# Audio.net
KiCad netlist of a schematic drawn in Altium Designer
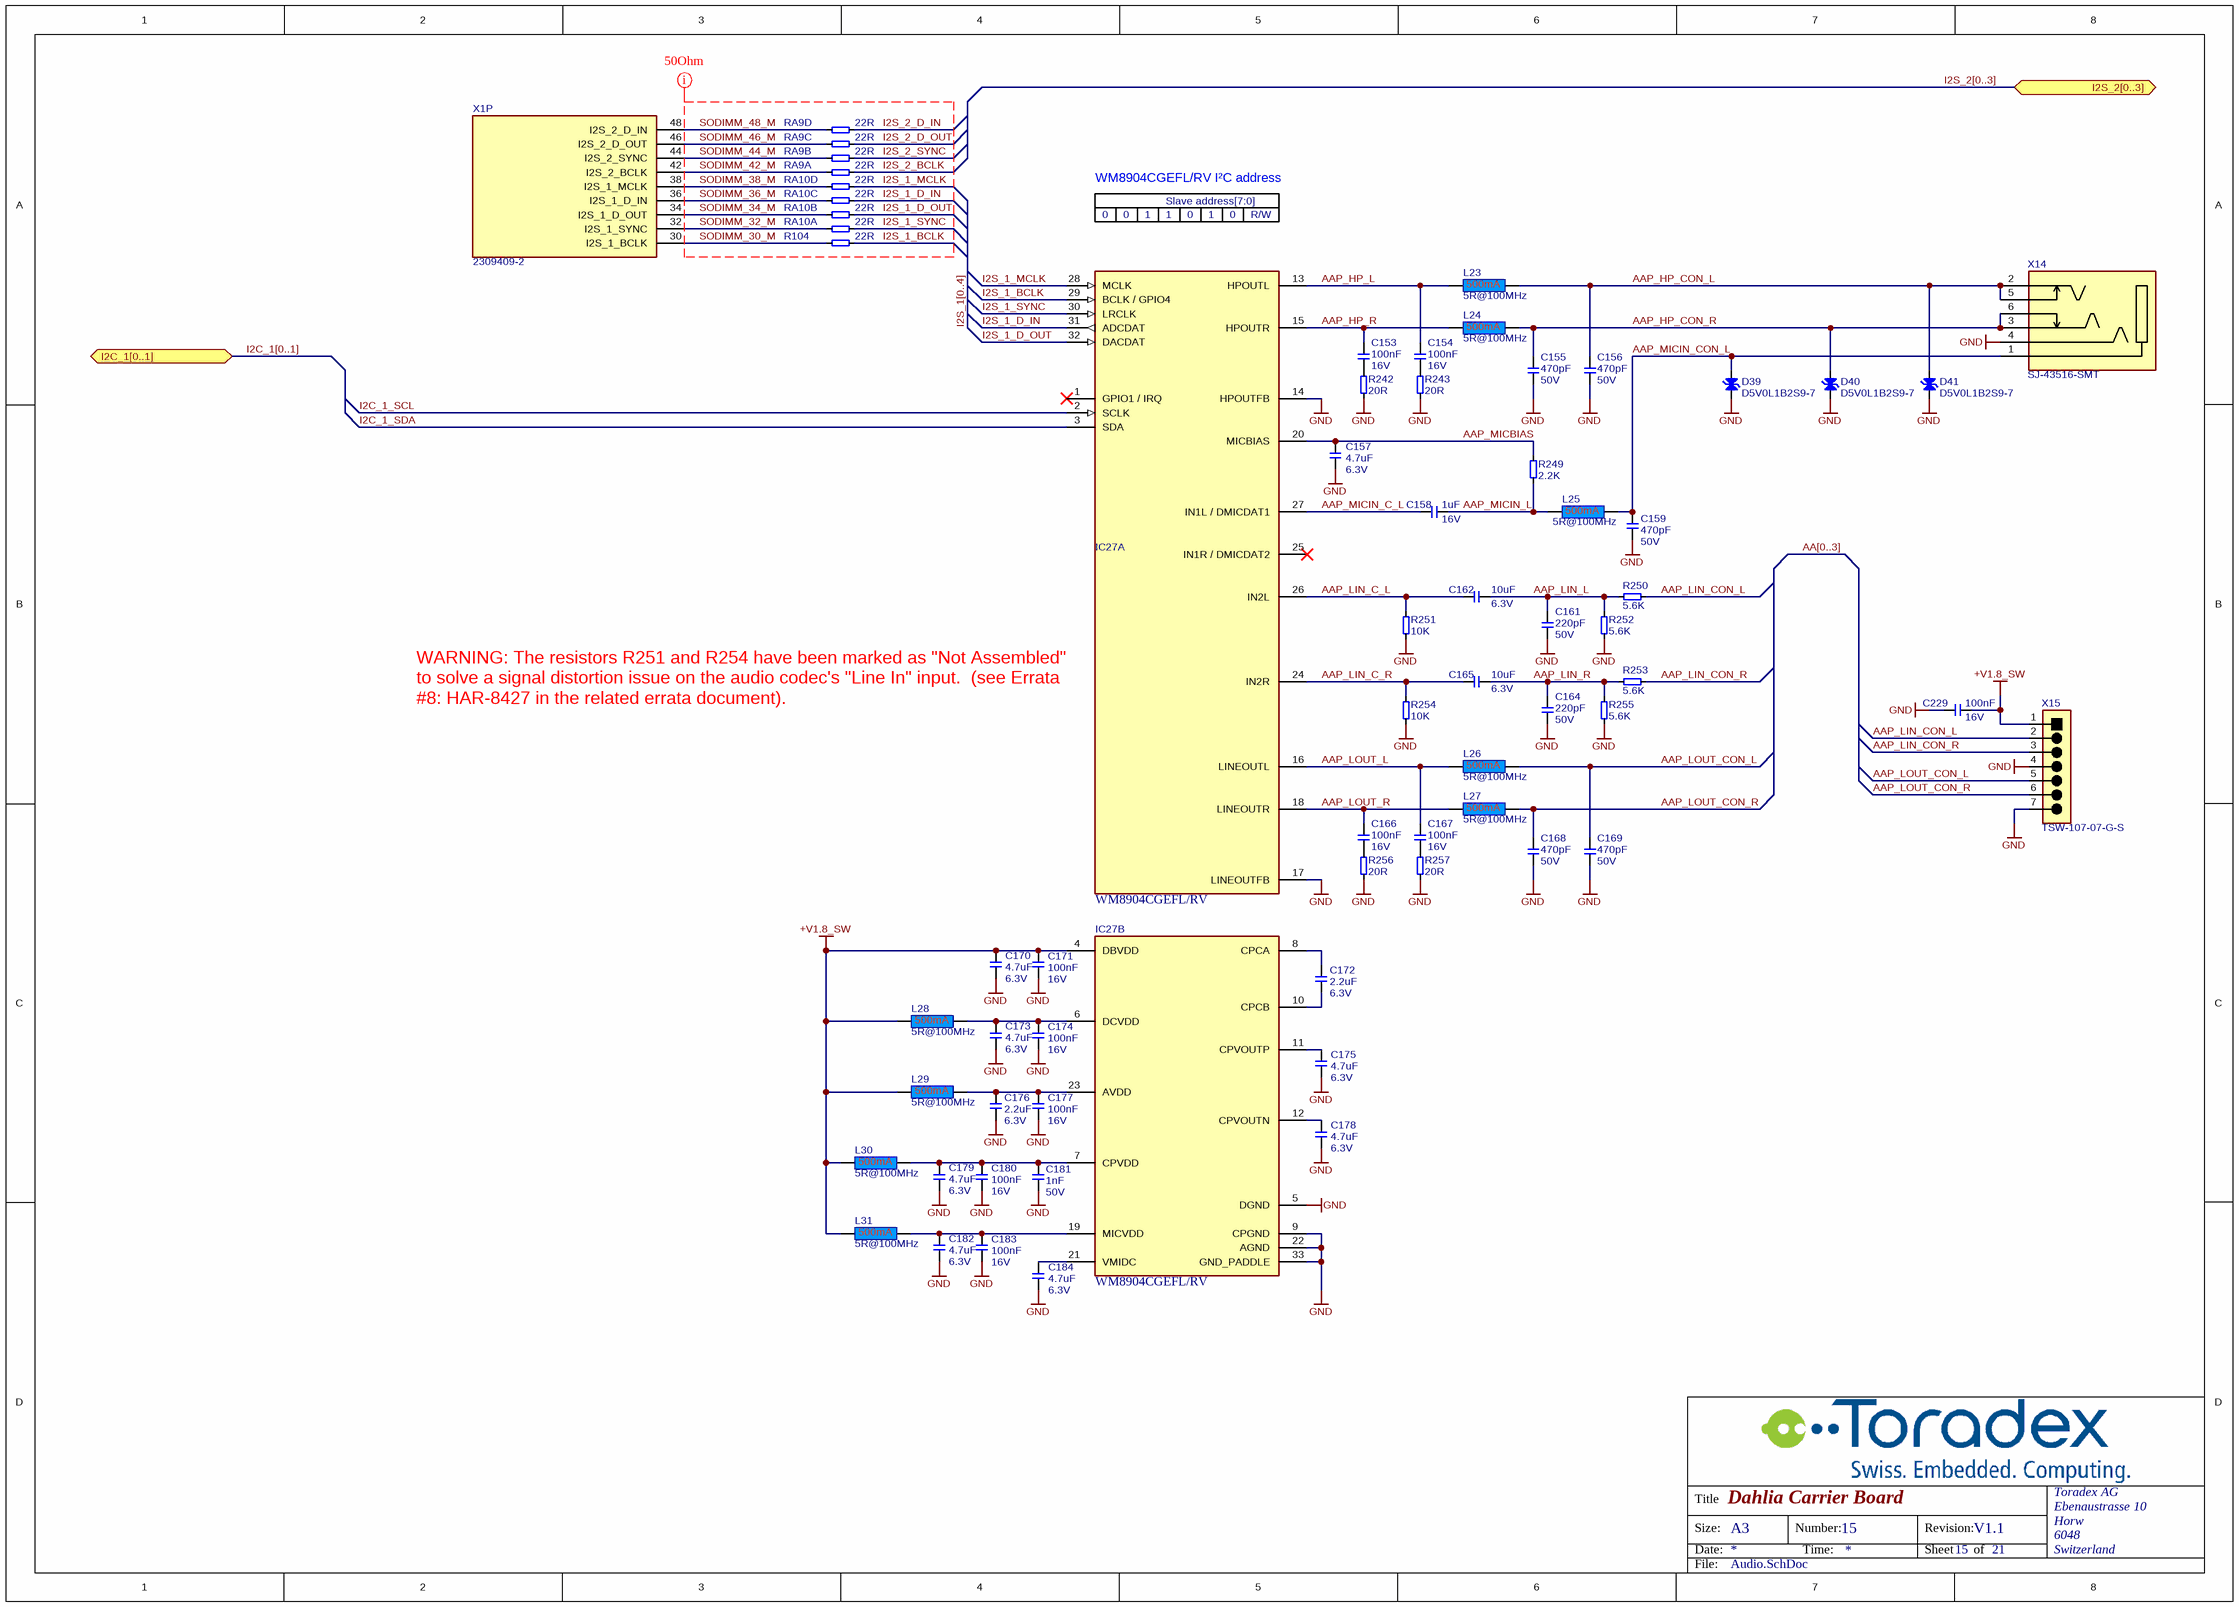
[diagram p0: Audio.SchDoc]

(export (version "E")
  (design (tool "Eeschema 10.0.6"))
  (components
    (comp (ref "C153")
      (value "100nF")
      (footprint "CAPC1005X60N")
      (description "Capacitor Ceramic X7R 100nF 16V 10% 0402")
      (fields (field (name "TOLERANCE") "10%") (field (name "RATING") "16V"))
      (libsource (lib "Dahlia Carrier Board") (part "C-X7R-100nF-16V-10%-0402"))
    )
    (comp (ref "C154")
      (value "100nF")
      (footprint "CAPC1005X60N")
      (description "Capacitor Ceramic X7R 100nF 16V 10% 0402")
      (fields (field (name "TOLERANCE") "10%") (field (name "RATING") "16V"))
      (libsource (lib "Dahlia Carrier Board") (part "C-X7R-100nF-16V-10%-0402"))
    )
    (comp (ref "C155")
      (value "470pF")
      (footprint "CAPC1005X60N")
      (description "Capacitor Ceramic X7R 470pF 50V 10% 0402")
      (fields (field (name "TOLERANCE") "10%") (field (name "RATING") "50V"))
      (libsource (lib "Dahlia Carrier Board") (part "C-X7R-470p-50V-10%-0402"))
    )
    (comp (ref "C156")
      (value "470pF")
      (footprint "CAPC1005X60N")
      (description "Capacitor Ceramic X7R 470pF 50V 10% 0402")
      (fields (field (name "TOLERANCE") "10%") (field (name "RATING") "50V"))
      (libsource (lib "Dahlia Carrier Board") (part "C-X7R-470p-50V-10%-0402"))
    )
    (comp (ref "C157")
      (value "4.7uF")
      (footprint "CAPC1005X60N")
      (description "Capacitor Ceramic X5R 4.7uF 6.3V 20% 0402")
      (fields (field (name "TOLERANCE") "20%") (field (name "RATING") "6.3V"))
      (libsource (lib "Dahlia Carrier Board") (part "C-X5R-4.7u-6.3V-20%-0402"))
    )
    (comp (ref "C158")
      (value "1uF")
      (footprint "CAPC1005X60N")
      (description "Capacitor Ceramic X5R 1uF 16V 20% 0402")
      (fields (field (name "TOLERANCE") "20%") (field (name "RATING") "16V"))
      (libsource (lib "Dahlia Carrier Board") (part "C-X5R-1uF-16V-20%-0402"))
    )
    (comp (ref "C159")
      (value "470pF")
      (footprint "CAPC1005X60N")
      (description "Capacitor Ceramic X7R 470pF 50V 10% 0402")
      (fields (field (name "TOLERANCE") "10%") (field (name "RATING") "50V"))
      (libsource (lib "Dahlia Carrier Board") (part "C-X7R-470p-50V-10%-0402"))
    )
    (comp (ref "C161")
      (value "220pF")
      (footprint "CAPC1005X60N")
      (description "Capacitor Ceramic X7R  220pF 50V 10% 0402")
      (fields (field (name "TOLERANCE") "10%") (field (name "RATING") "50V"))
      (libsource (lib "Dahlia Carrier Board") (part "C-X7R-220pF-50V-10%-0402"))
    )
    (comp (ref "C162")
      (value "10uF")
      (footprint "CAPC1005X60N")
      (description "Capacitor Ceramic X5R 10uF 6.3V 20% 0402")
      (fields (field (name "TOLERANCE") "20%") (field (name "RATING") "6.3V"))
      (libsource (lib "Dahlia Carrier Board") (part "C-X5R-10u-6.3V-20%-0402"))
    )
    (comp (ref "C164")
      (value "220pF")
      (footprint "CAPC1005X60N")
      (description "Capacitor Ceramic X7R  220pF 50V 10% 0402")
      (fields (field (name "TOLERANCE") "10%") (field (name "RATING") "50V"))
      (libsource (lib "Dahlia Carrier Board") (part "C-X7R-220pF-50V-10%-0402"))
    )
    (comp (ref "C165")
      (value "10uF")
      (footprint "CAPC1005X60N")
      (description "Capacitor Ceramic X5R 10uF 6.3V 20% 0402")
      (fields (field (name "TOLERANCE") "20%") (field (name "RATING") "6.3V"))
      (libsource (lib "Dahlia Carrier Board") (part "C-X5R-10u-6.3V-20%-0402"))
    )
    (comp (ref "C166")
      (value "100nF")
      (footprint "CAPC1005X60N")
      (description "Capacitor Ceramic X7R 100nF 16V 10% 0402")
      (fields (field (name "TOLERANCE") "10%") (field (name "RATING") "16V"))
      (libsource (lib "Dahlia Carrier Board") (part "C-X7R-100nF-16V-10%-0402"))
    )
    (comp (ref "C167")
      (value "100nF")
      (footprint "CAPC1005X60N")
      (description "Capacitor Ceramic X7R 100nF 16V 10% 0402")
      (fields (field (name "TOLERANCE") "10%") (field (name "RATING") "16V"))
      (libsource (lib "Dahlia Carrier Board") (part "C-X7R-100nF-16V-10%-0402"))
    )
    (comp (ref "C168")
      (value "470pF")
      (footprint "CAPC1005X60N")
      (description "Capacitor Ceramic X7R 470pF 50V 10% 0402")
      (fields (field (name "TOLERANCE") "10%") (field (name "RATING") "50V"))
      (libsource (lib "Dahlia Carrier Board") (part "C-X7R-470p-50V-10%-0402"))
    )
    (comp (ref "C169")
      (value "470pF")
      (footprint "CAPC1005X60N")
      (description "Capacitor Ceramic X7R 470pF 50V 10% 0402")
      (fields (field (name "TOLERANCE") "10%") (field (name "RATING") "50V"))
      (libsource (lib "Dahlia Carrier Board") (part "C-X7R-470p-50V-10%-0402"))
    )
    (comp (ref "C170")
      (value "4.7uF")
      (footprint "CAPC1005X60N")
      (description "Capacitor Ceramic X5R 4.7uF 6.3V 20% 0402")
      (fields (field (name "TOLERANCE") "20%") (field (name "RATING") "6.3V"))
      (libsource (lib "Dahlia Carrier Board") (part "C-X5R-4.7u-6.3V-20%-0402"))
    )
    (comp (ref "C171")
      (value "100nF")
      (footprint "CAPC1005X60N")
      (description "Capacitor Ceramic X7R 100nF 16V 10% 0402")
      (fields (field (name "TOLERANCE") "10%") (field (name "RATING") "16V"))
      (libsource (lib "Dahlia Carrier Board") (part "C-X7R-100nF-16V-10%-0402"))
    )
    (comp (ref "C172")
      (value "2.2uF")
      (footprint "CAPC1005X60N")
      (description "Capacitor Ceramic X5R 2.2uF 6.3V 20% 0402")
      (fields (field (name "TOLERANCE") "20%") (field (name "RATING") "6.3V"))
      (libsource (lib "Dahlia Carrier Board") (part "C-X5R-2.2u-6.3V-20%-0402"))
    )
    (comp (ref "C173")
      (value "4.7uF")
      (footprint "CAPC1005X60N")
      (description "Capacitor Ceramic X5R 4.7uF 6.3V 20% 0402")
      (fields (field (name "TOLERANCE") "20%") (field (name "RATING") "6.3V"))
      (libsource (lib "Dahlia Carrier Board") (part "C-X5R-4.7u-6.3V-20%-0402"))
    )
    (comp (ref "C174")
      (value "100nF")
      (footprint "CAPC1005X60N")
      (description "Capacitor Ceramic X7R 100nF 16V 10% 0402")
      (fields (field (name "TOLERANCE") "10%") (field (name "RATING") "16V"))
      (libsource (lib "Dahlia Carrier Board") (part "C-X7R-100nF-16V-10%-0402"))
    )
    (comp (ref "C175")
      (value "4.7uF")
      (footprint "CAPC1005X60N")
      (description "Capacitor Ceramic X5R 4.7uF 6.3V 20% 0402")
      (fields (field (name "TOLERANCE") "20%") (field (name "RATING") "6.3V"))
      (libsource (lib "Dahlia Carrier Board") (part "C-X5R-4.7u-6.3V-20%-0402"))
    )
    (comp (ref "C176")
      (value "2.2uF")
      (footprint "CAPC1005X60N")
      (description "Capacitor Ceramic X5R 2.2uF 6.3V 20% 0402")
      (fields (field (name "TOLERANCE") "20%") (field (name "RATING") "6.3V"))
      (libsource (lib "Dahlia Carrier Board") (part "C-X5R-2.2u-6.3V-20%-0402"))
    )
    (comp (ref "C177")
      (value "100nF")
      (footprint "CAPC1005X60N")
      (description "Capacitor Ceramic X7R 100nF 16V 10% 0402")
      (fields (field (name "TOLERANCE") "10%") (field (name "RATING") "16V"))
      (libsource (lib "Dahlia Carrier Board") (part "C-X7R-100nF-16V-10%-0402"))
    )
    (comp (ref "C178")
      (value "4.7uF")
      (footprint "CAPC1005X60N")
      (description "Capacitor Ceramic X5R 4.7uF 6.3V 20% 0402")
      (fields (field (name "TOLERANCE") "20%") (field (name "RATING") "6.3V"))
      (libsource (lib "Dahlia Carrier Board") (part "C-X5R-4.7u-6.3V-20%-0402"))
    )
    (comp (ref "C179")
      (value "4.7uF")
      (footprint "CAPC1005X60N")
      (description "Capacitor Ceramic X5R 4.7uF 6.3V 20% 0402")
      (fields (field (name "TOLERANCE") "20%") (field (name "RATING") "6.3V"))
      (libsource (lib "Dahlia Carrier Board") (part "C-X5R-4.7u-6.3V-20%-0402"))
    )
    (comp (ref "C180")
      (value "100nF")
      (footprint "CAPC1005X60N")
      (description "Capacitor Ceramic X7R 100nF 16V 10% 0402")
      (fields (field (name "TOLERANCE") "10%") (field (name "RATING") "16V"))
      (libsource (lib "Dahlia Carrier Board") (part "C-X7R-100nF-16V-10%-0402"))
    )
    (comp (ref "C181")
      (value "1nF")
      (footprint "CAPC1005X60N")
      (description "Capacitor Ceramic X7R 1nF 50V 10% 0402")
      (fields (field (name "TOLERANCE") "10%") (field (name "RATING") "50V"))
      (libsource (lib "Dahlia Carrier Board") (part "C-X7R-1nF-50V-10%-0402"))
    )
    (comp (ref "C182")
      (value "4.7uF")
      (footprint "CAPC1005X60N")
      (description "Capacitor Ceramic X5R 4.7uF 6.3V 20% 0402")
      (fields (field (name "TOLERANCE") "20%") (field (name "RATING") "6.3V"))
      (libsource (lib "Dahlia Carrier Board") (part "C-X5R-4.7u-6.3V-20%-0402"))
    )
    (comp (ref "C183")
      (value "100nF")
      (footprint "CAPC1005X60N")
      (description "Capacitor Ceramic X7R 100nF 16V 10% 0402")
      (fields (field (name "TOLERANCE") "10%") (field (name "RATING") "16V"))
      (libsource (lib "Dahlia Carrier Board") (part "C-X7R-100nF-16V-10%-0402"))
    )
    (comp (ref "C184")
      (value "4.7uF")
      (footprint "CAPC1005X60N")
      (description "Capacitor Ceramic X5R 4.7uF 6.3V 20% 0402")
      (fields (field (name "TOLERANCE") "20%") (field (name "RATING") "6.3V"))
      (libsource (lib "Dahlia Carrier Board") (part "C-X5R-4.7u-6.3V-20%-0402"))
    )
    (comp (ref "C229")
      (value "100nF")
      (footprint "CAPC1005X60N")
      (description "Capacitor Ceramic X7R 100nF 16V 10% 0402")
      (fields (field (name "TOLERANCE") "10%") (field (name "RATING") "16V"))
      (libsource (lib "Dahlia Carrier Board") (part "C-X7R-100nF-16V-10%-0402"))
    )
    (comp (ref "D39")
      (value "D5V0L1B2S9-7")
      (footprint "D-DIODES-SOD-923")
      (description "BIDIRECTIONAL TVS DIODE 5V  SOD923")
      (fields (field (name "MANUFACTURER PART NO.") "D5V0L1B2S9-7"))
      (libsource (lib "Dahlia Carrier Board") (part "D-Diodes-D5V0L1B2S9-7"))
    )
    (comp (ref "D40")
      (value "D5V0L1B2S9-7")
      (footprint "D-DIODES-SOD-923")
      (description "BIDIRECTIONAL TVS DIODE 5V  SOD923")
      (fields (field (name "MANUFACTURER PART NO.") "D5V0L1B2S9-7"))
      (libsource (lib "Dahlia Carrier Board") (part "D-Diodes-D5V0L1B2S9-7"))
    )
    (comp (ref "D41")
      (value "D5V0L1B2S9-7")
      (footprint "D-DIODES-SOD-923")
      (description "BIDIRECTIONAL TVS DIODE 5V  SOD923")
      (fields (field (name "MANUFACTURER PART NO.") "D5V0L1B2S9-7"))
      (libsource (lib "Dahlia Carrier Board") (part "D-Diodes-D5V0L1B2S9-7"))
    )
    (comp (ref "IC27")
      (value "WM8904CGEFL/RV")
      (footprint "IC-QFN40P400X400X80_HS-33N")
      (description "Stereo Audio Interface IC")
      (fields (field (name "MANUFACTURER PART NO.") "WM8904CGEFL/RV"))
      (libsource (lib "Dahlia Carrier Board") (part "IC-CIRRUS-WM8904CGEFL/RV"))
    )
    (comp (ref "L23")
      (value "5R@100MHz")
      (footprint "INDC1005X60N")
      (description "5R@100MHz 500mA EMI FILTER")
      (fields (field (name "TOLERANCE") "25%") (field (name "MANUFACTURER PART NO.") "BLM15BB050SN1D"))
      (libsource (lib "Dahlia Carrier Board") (part "Lemv-5R-500mA-25%-0402"))
    )
    (comp (ref "L24")
      (value "5R@100MHz")
      (footprint "INDC1005X60N")
      (description "5R@100MHz 500mA EMI FILTER")
      (fields (field (name "TOLERANCE") "25%") (field (name "MANUFACTURER PART NO.") "BLM15BB050SN1D"))
      (libsource (lib "Dahlia Carrier Board") (part "Lemv-5R-500mA-25%-0402"))
    )
    (comp (ref "L25")
      (value "5R@100MHz")
      (footprint "INDC1005X60N")
      (description "5R@100MHz 500mA EMI FILTER")
      (fields (field (name "TOLERANCE") "25%") (field (name "MANUFACTURER PART NO.") "BLM15BB050SN1D"))
      (libsource (lib "Dahlia Carrier Board") (part "Lemv-5R-500mA-25%-0402"))
    )
    (comp (ref "L26")
      (value "5R@100MHz")
      (footprint "INDC1005X60N")
      (description "5R@100MHz 500mA EMI FILTER")
      (fields (field (name "TOLERANCE") "25%") (field (name "MANUFACTURER PART NO.") "BLM15BB050SN1D"))
      (libsource (lib "Dahlia Carrier Board") (part "Lemv-5R-500mA-25%-0402"))
    )
    (comp (ref "L27")
      (value "5R@100MHz")
      (footprint "INDC1005X60N")
      (description "5R@100MHz 500mA EMI FILTER")
      (fields (field (name "TOLERANCE") "25%") (field (name "MANUFACTURER PART NO.") "BLM15BB050SN1D"))
      (libsource (lib "Dahlia Carrier Board") (part "Lemv-5R-500mA-25%-0402"))
    )
    (comp (ref "L28")
      (value "5R@100MHz")
      (footprint "INDC1005X60N")
      (description "5R@100MHz 500mA EMI FILTER")
      (fields (field (name "TOLERANCE") "25%") (field (name "MANUFACTURER PART NO.") "BLM15BB050SN1D"))
      (libsource (lib "Dahlia Carrier Board") (part "Lemv-5R-500mA-25%-0402"))
    )
    (comp (ref "L29")
      (value "5R@100MHz")
      (footprint "INDC1005X60N")
      (description "5R@100MHz 500mA EMI FILTER")
      (fields (field (name "TOLERANCE") "25%") (field (name "MANUFACTURER PART NO.") "BLM15BB050SN1D"))
      (libsource (lib "Dahlia Carrier Board") (part "Lemv-5R-500mA-25%-0402"))
    )
    (comp (ref "L30")
      (value "5R@100MHz")
      (footprint "INDC1005X60N")
      (description "5R@100MHz 500mA EMI FILTER")
      (fields (field (name "TOLERANCE") "25%") (field (name "MANUFACTURER PART NO.") "BLM15BB050SN1D"))
      (libsource (lib "Dahlia Carrier Board") (part "Lemv-5R-500mA-25%-0402"))
    )
    (comp (ref "L31")
      (value "5R@100MHz")
      (footprint "INDC1005X60N")
      (description "5R@100MHz 500mA EMI FILTER")
      (fields (field (name "TOLERANCE") "25%") (field (name "MANUFACTURER PART NO.") "BLM15BB050SN1D"))
      (libsource (lib "Dahlia Carrier Board") (part "Lemv-5R-500mA-25%-0402"))
    )
    (comp (ref "R104")
      (value "22R")
      (footprint "RESC1005X40N")
      (description "Resistor 22 ohm 63mW 5% 0402")
      (fields (field (name "TOLERANCE") "5%"))
      (libsource (lib "Dahlia Carrier Board") (part "R-22R-63mW-5%-0402"))
    )
    (comp (ref "R242")
      (value "20R")
      (footprint "RESC1005X40N")
      (description "Resistor 20 ohm 63mW 5% 0402")
      (fields (field (name "TOLERANCE") "5%"))
      (libsource (lib "Dahlia Carrier Board") (part "R-20R-63mW-5%-0402"))
    )
    (comp (ref "R243")
      (value "20R")
      (footprint "RESC1005X40N")
      (description "Resistor 20 ohm 63mW 5% 0402")
      (fields (field (name "TOLERANCE") "5%"))
      (libsource (lib "Dahlia Carrier Board") (part "R-20R-63mW-5%-0402"))
    )
    (comp (ref "R249")
      (value "2.2K")
      (footprint "RESC1005X40N")
      (description "Resistor 2.2 Kohm 63mW 5% 0402")
      (fields (field (name "TOLERANCE") "5%"))
      (libsource (lib "Dahlia Carrier Board") (part "R-2.2K-63mW-5%-0402"))
    )
    (comp (ref "R250")
      (value "5.6K")
      (footprint "RESC1005X40N")
      (description "Resistor 5.6 Kohm 63mW 5% 0402")
      (fields (field (name "TOLERANCE") "5%"))
      (libsource (lib "Dahlia Carrier Board") (part "R-5.6K-63mW-5%-0402"))
    )
    (comp (ref "R251")
      (value "10K")
      (footprint "RESC1005X40N")
      (description "Resistor 10 Kohm 63mW 5% 0402")
      (fields (field (name "TOLERANCE") "5%"))
      (libsource (lib "Dahlia Carrier Board") (part "R-10K-63mW-5%-0402"))
    )
    (comp (ref "R252")
      (value "5.6K")
      (footprint "RESC1005X40N")
      (description "Resistor 5.6 Kohm 63mW 5% 0402")
      (fields (field (name "TOLERANCE") "5%"))
      (libsource (lib "Dahlia Carrier Board") (part "R-5.6K-63mW-5%-0402"))
    )
    (comp (ref "R253")
      (value "5.6K")
      (footprint "RESC1005X40N")
      (description "Resistor 5.6 Kohm 63mW 5% 0402")
      (fields (field (name "TOLERANCE") "5%"))
      (libsource (lib "Dahlia Carrier Board") (part "R-5.6K-63mW-5%-0402"))
    )
    (comp (ref "R254")
      (value "10K")
      (footprint "RESC1005X40N")
      (description "Resistor 10 Kohm 63mW 5% 0402")
      (fields (field (name "TOLERANCE") "5%"))
      (libsource (lib "Dahlia Carrier Board") (part "R-10K-63mW-5%-0402"))
    )
    (comp (ref "R255")
      (value "5.6K")
      (footprint "RESC1005X40N")
      (description "Resistor 5.6 Kohm 63mW 5% 0402")
      (fields (field (name "TOLERANCE") "5%"))
      (libsource (lib "Dahlia Carrier Board") (part "R-5.6K-63mW-5%-0402"))
    )
    (comp (ref "R256")
      (value "20R")
      (footprint "RESC1005X40N")
      (description "Resistor 20 ohm 63mW 5% 0402")
      (fields (field (name "TOLERANCE") "5%"))
      (libsource (lib "Dahlia Carrier Board") (part "R-20R-63mW-5%-0402"))
    )
    (comp (ref "R257")
      (value "20R")
      (footprint "RESC1005X40N")
      (description "Resistor 20 ohm 63mW 5% 0402")
      (fields (field (name "TOLERANCE") "5%"))
      (libsource (lib "Dahlia Carrier Board") (part "R-20R-63mW-5%-0402"))
    )
    (comp (ref "RA9")
      (value "22R")
      (footprint "T_Resistor_Array_X4")
      (description "Resistor Array 22 R 63mW 5% 1206")
      (fields (field (name "TOLERANCE") "5%"))
      (libsource (lib "Dahlia Carrier Board") (part "RA-22R-63mW-5%-1206-div"))
    )
    (comp (ref "RA10")
      (value "22R")
      (footprint "T_Resistor_Array_X4")
      (description "Resistor Array 22 R 63mW 5% 1206")
      (fields (field (name "TOLERANCE") "5%"))
      (libsource (lib "Dahlia Carrier Board") (part "RA-22R-63mW-5%-1206-div"))
    )
    (comp (ref "X1")
      (value "2309409-2")
      (footprint "CON-TE-2309409-2-SOLDERABLE-STANDOFFS")
      (description "DDR4 SODIMM Socket, 260 pins, 5.2mm(H), 0.5mm Pitch")
      (libsource (lib "Dahlia Carrier Board") (part "CON-TE-2309409-2"))
    )
    (comp (ref "X14")
      (value "SJ-43516-SMT")
      (footprint "T_CI_SJ-43516-SMT")
      (description "3.5mm Stereo Jack SMD With Detect Contact")
      (fields (field (name "MANUFACTURER PART NO.") "SJ-43516-SMT"))
      (libsource (lib "Dahlia Carrier Board") (part "CON-Cui-SJ-43516-SMT-6-3.5mm"))
    )
    (comp (ref "X15")
      (value "TSW-107-07-G-S")
      (footprint "T_Samtec_TSW-107-07-G-S")
      (description "Header male, 1X7 Pins, 2.54 mm pitch")
      (fields (field (name "MANUFACTURER PART NO.") "TSW-107-07-G-S"))
      (libsource (lib "Dahlia Carrier Board") (part "CON-Samtec-TSW-107-07-G-S"))
    )
  )
  (nets
    (net (code "16") (name "+V1.8_SW") (class "Default")
      (node (ref "C170") (pin "2") (pinfunction "2_2") (pintype "passive"))
      (node (ref "C171") (pin "2") (pinfunction "2_2") (pintype "passive"))
      (node (ref "C229") (pin "1") (pinfunction "1_1") (pintype "passive"))
      (node (ref "IC27") (pin "4") (pinfunction "DBVDD_4") (pintype "passive"))
      (node (ref "L28") (pin "1") (pinfunction "1_1") (pintype "passive"))
      (node (ref "L29") (pin "1") (pinfunction "1_1") (pintype "passive"))
      (node (ref "L30") (pin "1") (pinfunction "1_1") (pintype "passive"))
      (node (ref "L31") (pin "1") (pinfunction "1_1") (pintype "passive"))
      (node (ref "X15") (pin "1") (pinfunction "1_1") (pintype "passive"))
    )
    (net (code "17") (name "/AAP_HP_CON_L") (class "Default")
      (node (ref "C156") (pin "2") (pinfunction "2_2") (pintype "passive"))
      (node (ref "D41") (pin "2") (pinfunction "A_2") (pintype "power_in"))
      (node (ref "L23") (pin "2") (pinfunction "2_2") (pintype "passive"))
      (node (ref "X14") (pin "2") (pinfunction "2_2") (pintype "passive"))
      (node (ref "X14") (pin "5") (pinfunction "5_5") (pintype "passive"))
    )
    (net (code "18") (name "/AAP_HP_CON_R") (class "Default")
      (node (ref "C155") (pin "2") (pinfunction "2_2") (pintype "passive"))
      (node (ref "D40") (pin "2") (pinfunction "A_2") (pintype "power_in"))
      (node (ref "L24") (pin "2") (pinfunction "2_2") (pintype "passive"))
      (node (ref "X14") (pin "3") (pinfunction "3_3") (pintype "passive"))
      (node (ref "X14") (pin "6") (pinfunction "6_6") (pintype "passive"))
    )
    (net (code "19") (name "/AAP_HP_L") (class "Default")
      (node (ref "C154") (pin "2") (pinfunction "2_2") (pintype "passive"))
      (node (ref "IC27") (pin "13") (pinfunction "HPOUTL_13") (pintype "passive"))
      (node (ref "L23") (pin "1") (pinfunction "1_1") (pintype "passive"))
    )
    (net (code "20") (name "/AAP_HP_R") (class "Default")
      (node (ref "C153") (pin "2") (pinfunction "2_2") (pintype "passive"))
      (node (ref "IC27") (pin "15") (pinfunction "HPOUTR_15") (pintype "passive"))
      (node (ref "L24") (pin "1") (pinfunction "1_1") (pintype "passive"))
    )
    (net (code "21") (name "/AAP_LIN_CON_L") (class "Default")
      (node (ref "R250") (pin "1") (pinfunction "1_1") (pintype "passive"))
      (node (ref "X15") (pin "2") (pinfunction "2_2") (pintype "passive"))
    )
    (net (code "22") (name "/AAP_LIN_CON_R") (class "Default")
      (node (ref "R253") (pin "1") (pinfunction "1_1") (pintype "passive"))
      (node (ref "X15") (pin "3") (pinfunction "3_3") (pintype "passive"))
    )
    (net (code "23") (name "/AAP_LIN_C_L") (class "Default")
      (node (ref "C162") (pin "2") (pinfunction "2_2") (pintype "passive"))
      (node (ref "IC27") (pin "26") (pinfunction "IN2L_26") (pintype "passive"))
      (node (ref "R251") (pin "2") (pinfunction "2_2") (pintype "passive"))
    )
    (net (code "24") (name "/AAP_LIN_C_R") (class "Default")
      (node (ref "C165") (pin "2") (pinfunction "2_2") (pintype "passive"))
      (node (ref "IC27") (pin "24") (pinfunction "IN2R_24") (pintype "passive"))
      (node (ref "R254") (pin "2") (pinfunction "2_2") (pintype "passive"))
    )
    (net (code "25") (name "/AAP_LIN_L") (class "Default")
      (node (ref "C161") (pin "2") (pinfunction "2_2") (pintype "passive"))
      (node (ref "C162") (pin "1") (pinfunction "1_1") (pintype "passive"))
      (node (ref "R250") (pin "2") (pinfunction "2_2") (pintype "passive"))
      (node (ref "R252") (pin "2") (pinfunction "2_2") (pintype "passive"))
    )
    (net (code "26") (name "/AAP_LIN_R") (class "Default")
      (node (ref "C164") (pin "2") (pinfunction "2_2") (pintype "passive"))
      (node (ref "C165") (pin "1") (pinfunction "1_1") (pintype "passive"))
      (node (ref "R253") (pin "2") (pinfunction "2_2") (pintype "passive"))
      (node (ref "R255") (pin "2") (pinfunction "2_2") (pintype "passive"))
    )
    (net (code "27") (name "/AAP_LOUT_CON_L") (class "Default")
      (node (ref "C169") (pin "2") (pinfunction "2_2") (pintype "passive"))
      (node (ref "L26") (pin "2") (pinfunction "2_2") (pintype "passive"))
      (node (ref "X15") (pin "5") (pinfunction "5_5") (pintype "passive"))
    )
    (net (code "28") (name "/AAP_LOUT_CON_R") (class "Default")
      (node (ref "C168") (pin "2") (pinfunction "2_2") (pintype "passive"))
      (node (ref "L27") (pin "2") (pinfunction "2_2") (pintype "passive"))
      (node (ref "X15") (pin "6") (pinfunction "6_6") (pintype "passive"))
    )
    (net (code "29") (name "/AAP_LOUT_L") (class "Default")
      (node (ref "C167") (pin "2") (pinfunction "2_2") (pintype "passive"))
      (node (ref "IC27") (pin "16") (pinfunction "LINEOUTL_16") (pintype "passive"))
      (node (ref "L26") (pin "1") (pinfunction "1_1") (pintype "passive"))
    )
    (net (code "30") (name "/AAP_LOUT_R") (class "Default")
      (node (ref "C166") (pin "2") (pinfunction "2_2") (pintype "passive"))
      (node (ref "IC27") (pin "18") (pinfunction "LINEOUTR_18") (pintype "passive"))
      (node (ref "L27") (pin "1") (pinfunction "1_1") (pintype "passive"))
    )
    (net (code "31") (name "/AAP_MICBIAS") (class "Default")
      (node (ref "C157") (pin "2") (pinfunction "2_2") (pintype "passive"))
      (node (ref "IC27") (pin "20") (pinfunction "MICBIAS_20") (pintype "passive"))
      (node (ref "R249") (pin "2") (pinfunction "2_2") (pintype "passive"))
    )
    (net (code "32") (name "/AAP_MICIN_CON_L") (class "Default")
      (node (ref "C159") (pin "2") (pinfunction "2_2") (pintype "passive"))
      (node (ref "D39") (pin "2") (pinfunction "A_2") (pintype "power_in"))
      (node (ref "L25") (pin "2") (pinfunction "2_2") (pintype "passive"))
      (node (ref "X14") (pin "1") (pinfunction "1_1") (pintype "passive"))
    )
    (net (code "33") (name "/AAP_MICIN_C_L") (class "Default")
      (node (ref "C158") (pin "1") (pinfunction "1_1") (pintype "passive"))
      (node (ref "IC27") (pin "27") (pinfunction "IN1L_/_DMICDAT1_27") (pintype "passive"))
    )
    (net (code "34") (name "/AAP_MICIN_L") (class "Default")
      (node (ref "C158") (pin "2") (pinfunction "2_2") (pintype "passive"))
      (node (ref "L25") (pin "1") (pinfunction "1_1") (pintype "passive"))
      (node (ref "R249") (pin "1") (pinfunction "1_1") (pintype "passive"))
    )
    (net (code "37") (name "/I2C_1_SCL") (class "Default")
      (node (ref "IC27") (pin "2") (pinfunction "SCLK_2") (pintype "input"))
    )
    (net (code "38") (name "/I2C_1_SDA") (class "Default")
      (node (ref "IC27") (pin "3") (pinfunction "SDA_3") (pintype "passive"))
    )
    (net (code "40") (name "/I2S_1_BCLK") (class "Default")
      (node (ref "IC27") (pin "29") (pinfunction "BCLK_/_GPIO4_29") (pintype "input"))
      (node (ref "R104") (pin "2") (pinfunction "2_2") (pintype "passive"))
    )
    (net (code "41") (name "/I2S_1_D_IN") (class "Default")
      (node (ref "IC27") (pin "31") (pinfunction "ADCDAT_31") (pintype "output"))
      (node (ref "RA10") (pin "7") (pinfunction "7_7") (pintype "passive"))
    )
    (net (code "42") (name "/I2S_1_D_OUT") (class "Default")
      (node (ref "IC27") (pin "32") (pinfunction "DACDAT_32") (pintype "input"))
      (node (ref "RA10") (pin "6") (pinfunction "6_6") (pintype "passive"))
    )
    (net (code "43") (name "/I2S_1_MCLK") (class "Default")
      (node (ref "IC27") (pin "28") (pinfunction "MCLK_28") (pintype "input"))
      (node (ref "RA10") (pin "8") (pinfunction "8_8") (pintype "passive"))
    )
    (net (code "44") (name "/I2S_1_SYNC") (class "Default")
      (node (ref "IC27") (pin "30") (pinfunction "LRCLK_30") (pintype "input"))
      (node (ref "RA10") (pin "5") (pinfunction "5_5") (pintype "passive"))
    )
    (net (code "46") (name "/I2S_2_BCLK") (class "Default")
      (node (ref "RA9") (pin "5") (pinfunction "5_5") (pintype "passive"))
    )
    (net (code "47") (name "/I2S_2_D_IN") (class "Default")
      (node (ref "RA9") (pin "8") (pinfunction "8_8") (pintype "passive"))
    )
    (net (code "48") (name "/I2S_2_D_OUT") (class "Default")
      (node (ref "RA9") (pin "7") (pinfunction "7_7") (pintype "passive"))
    )
    (net (code "49") (name "/I2S_2_SYNC") (class "Default")
      (node (ref "RA9") (pin "6") (pinfunction "6_6") (pintype "passive"))
    )
    (net (code "50") (name "/SODIMM_30_M") (class "Default")
      (node (ref "R104") (pin "1") (pinfunction "1_1") (pintype "passive"))
      (node (ref "X1") (pin "30") (pinfunction "I2S_1_BCLK_30") (pintype "passive"))
    )
    (net (code "51") (name "/SODIMM_32_M") (class "Default")
      (node (ref "RA10") (pin "1") (pinfunction "1_1") (pintype "passive"))
      (node (ref "X1") (pin "32") (pinfunction "I2S_1_SYNC_32") (pintype "passive"))
    )
    (net (code "52") (name "/SODIMM_34_M") (class "Default")
      (node (ref "RA10") (pin "2") (pinfunction "2_2") (pintype "passive"))
      (node (ref "X1") (pin "34") (pinfunction "I2S_1_D_OUT_34") (pintype "passive"))
    )
    (net (code "53") (name "/SODIMM_36_M") (class "Default")
      (node (ref "RA10") (pin "3") (pinfunction "3_3") (pintype "passive"))
      (node (ref "X1") (pin "36") (pinfunction "I2S_1_D_IN_36") (pintype "passive"))
    )
    (net (code "54") (name "/SODIMM_38_M") (class "Default")
      (node (ref "RA10") (pin "4") (pinfunction "4_4") (pintype "passive"))
      (node (ref "X1") (pin "38") (pinfunction "I2S_1_MCLK_38") (pintype "passive"))
    )
    (net (code "55") (name "/SODIMM_42_M") (class "Default")
      (node (ref "RA9") (pin "1") (pinfunction "1_1") (pintype "passive"))
      (node (ref "X1") (pin "42") (pinfunction "I2S_2_BCLK_42") (pintype "passive"))
    )
    (net (code "56") (name "/SODIMM_44_M") (class "Default")
      (node (ref "RA9") (pin "2") (pinfunction "2_2") (pintype "passive"))
      (node (ref "X1") (pin "44") (pinfunction "I2S_2_SYNC_44") (pintype "passive"))
    )
    (net (code "57") (name "/SODIMM_46_M") (class "Default")
      (node (ref "RA9") (pin "3") (pinfunction "3_3") (pintype "passive"))
      (node (ref "X1") (pin "46") (pinfunction "I2S_2_D_OUT_46") (pintype "passive"))
    )
    (net (code "58") (name "/SODIMM_48_M") (class "Default")
      (node (ref "RA9") (pin "4") (pinfunction "4_4") (pintype "passive"))
      (node (ref "X1") (pin "48") (pinfunction "I2S_2_D_IN_48") (pintype "passive"))
    )
    (net (code "59") (name "GND") (class "Default")
      (node (ref "C155") (pin "1") (pinfunction "1_1") (pintype "passive"))
      (node (ref "C156") (pin "1") (pinfunction "1_1") (pintype "passive"))
      (node (ref "C157") (pin "1") (pinfunction "1_1") (pintype "passive"))
      (node (ref "C159") (pin "1") (pinfunction "1_1") (pintype "passive"))
      (node (ref "C161") (pin "1") (pinfunction "1_1") (pintype "passive"))
      (node (ref "C164") (pin "1") (pinfunction "1_1") (pintype "passive"))
      (node (ref "C168") (pin "1") (pinfunction "1_1") (pintype "passive"))
      (node (ref "C169") (pin "1") (pinfunction "1_1") (pintype "passive"))
      (node (ref "C170") (pin "1") (pinfunction "1_1") (pintype "passive"))
      (node (ref "C171") (pin "1") (pinfunction "1_1") (pintype "passive"))
      (node (ref "C173") (pin "1") (pinfunction "1_1") (pintype "passive"))
      (node (ref "C174") (pin "1") (pinfunction "1_1") (pintype "passive"))
      (node (ref "C175") (pin "1") (pinfunction "1_1") (pintype "passive"))
      (node (ref "C176") (pin "1") (pinfunction "1_1") (pintype "passive"))
      (node (ref "C177") (pin "1") (pinfunction "1_1") (pintype "passive"))
      (node (ref "C178") (pin "1") (pinfunction "1_1") (pintype "passive"))
      (node (ref "C179") (pin "1") (pinfunction "1_1") (pintype "passive"))
      (node (ref "C180") (pin "1") (pinfunction "1_1") (pintype "passive"))
      (node (ref "C181") (pin "1") (pinfunction "1_1") (pintype "passive"))
      (node (ref "C182") (pin "1") (pinfunction "1_1") (pintype "passive"))
      (node (ref "C183") (pin "1") (pinfunction "1_1") (pintype "passive"))
      (node (ref "C184") (pin "1") (pinfunction "1_1") (pintype "passive"))
      (node (ref "C229") (pin "2") (pinfunction "2_2") (pintype "passive"))
      (node (ref "D39") (pin "1") (pinfunction "C_1") (pintype "power_in"))
      (node (ref "D40") (pin "1") (pinfunction "C_1") (pintype "power_in"))
      (node (ref "D41") (pin "1") (pinfunction "C_1") (pintype "power_in"))
      (node (ref "IC27") (pin "14") (pinfunction "HPOUTFB_14") (pintype "passive"))
      (node (ref "IC27") (pin "17") (pinfunction "LINEOUTFB_17") (pintype "passive"))
      (node (ref "IC27") (pin "22") (pinfunction "AGND_22") (pintype "passive"))
      (node (ref "IC27") (pin "33") (pinfunction "GND_PADDLE_33") (pintype "passive"))
      (node (ref "IC27") (pin "5") (pinfunction "DGND_5") (pintype "passive"))
      (node (ref "IC27") (pin "9") (pinfunction "CPGND_9") (pintype "passive"))
      (node (ref "R242") (pin "1") (pinfunction "1_1") (pintype "passive"))
      (node (ref "R243") (pin "1") (pinfunction "1_1") (pintype "passive"))
      (node (ref "R251") (pin "1") (pinfunction "1_1") (pintype "passive"))
      (node (ref "R252") (pin "1") (pinfunction "1_1") (pintype "passive"))
      (node (ref "R254") (pin "1") (pinfunction "1_1") (pintype "passive"))
      (node (ref "R255") (pin "1") (pinfunction "1_1") (pintype "passive"))
      (node (ref "R256") (pin "1") (pinfunction "1_1") (pintype "passive"))
      (node (ref "R257") (pin "1") (pinfunction "1_1") (pintype "passive"))
      (node (ref "X14") (pin "4") (pinfunction "4_4") (pintype "passive"))
      (node (ref "X15") (pin "4") (pinfunction "4_4") (pintype "passive"))
      (node (ref "X15") (pin "7") (pinfunction "7_7") (pintype "passive"))
    )
    (net (code "60") (name "Net-(C153-Pad1)") (class "Default")
      (node (ref "C153") (pin "1") (pinfunction "1_1") (pintype "passive"))
      (node (ref "R242") (pin "2") (pinfunction "2_2") (pintype "passive"))
    )
    (net (code "61") (name "Net-(C154-Pad1)") (class "Default")
      (node (ref "C154") (pin "1") (pinfunction "1_1") (pintype "passive"))
      (node (ref "R243") (pin "2") (pinfunction "2_2") (pintype "passive"))
    )
    (net (code "62") (name "Net-(C166-Pad1)") (class "Default")
      (node (ref "C166") (pin "1") (pinfunction "1_1") (pintype "passive"))
      (node (ref "R256") (pin "2") (pinfunction "2_2") (pintype "passive"))
    )
    (net (code "63") (name "Net-(C167-Pad1)") (class "Default")
      (node (ref "C167") (pin "1") (pinfunction "1_1") (pintype "passive"))
      (node (ref "R257") (pin "2") (pinfunction "2_2") (pintype "passive"))
    )
    (net (code "64") (name "Net-(IC27B-AVDD)") (class "Default")
      (node (ref "C176") (pin "2") (pinfunction "2_2") (pintype "passive"))
      (node (ref "C177") (pin "2") (pinfunction "2_2") (pintype "passive"))
      (node (ref "IC27") (pin "23") (pinfunction "AVDD_23") (pintype "passive"))
      (node (ref "L29") (pin "2") (pinfunction "2_2") (pintype "passive"))
    )
    (net (code "65") (name "Net-(IC27B-CPCA)") (class "Default")
      (node (ref "C172") (pin "2") (pinfunction "2_2") (pintype "passive"))
      (node (ref "IC27") (pin "8") (pinfunction "CPCA_8") (pintype "passive"))
    )
    (net (code "66") (name "Net-(IC27B-CPCB)") (class "Default")
      (node (ref "C172") (pin "1") (pinfunction "1_1") (pintype "passive"))
      (node (ref "IC27") (pin "10") (pinfunction "CPCB_10") (pintype "passive"))
    )
    (net (code "67") (name "Net-(IC27B-CPVDD)") (class "Default")
      (node (ref "C179") (pin "2") (pinfunction "2_2") (pintype "passive"))
      (node (ref "C180") (pin "2") (pinfunction "2_2") (pintype "passive"))
      (node (ref "C181") (pin "2") (pinfunction "2_2") (pintype "passive"))
      (node (ref "IC27") (pin "7") (pinfunction "CPVDD_7") (pintype "passive"))
      (node (ref "L30") (pin "2") (pinfunction "2_2") (pintype "passive"))
    )
    (net (code "68") (name "Net-(IC27B-CPVOUTN)") (class "Default")
      (node (ref "C178") (pin "2") (pinfunction "2_2") (pintype "passive"))
      (node (ref "IC27") (pin "12") (pinfunction "CPVOUTN_12") (pintype "passive"))
    )
    (net (code "69") (name "Net-(IC27B-CPVOUTP)") (class "Default")
      (node (ref "C175") (pin "2") (pinfunction "2_2") (pintype "passive"))
      (node (ref "IC27") (pin "11") (pinfunction "CPVOUTP_11") (pintype "passive"))
    )
    (net (code "70") (name "Net-(IC27B-DCVDD)") (class "Default")
      (node (ref "C173") (pin "2") (pinfunction "2_2") (pintype "passive"))
      (node (ref "C174") (pin "2") (pinfunction "2_2") (pintype "passive"))
      (node (ref "IC27") (pin "6") (pinfunction "DCVDD_6") (pintype "passive"))
      (node (ref "L28") (pin "2") (pinfunction "2_2") (pintype "passive"))
    )
    (net (code "71") (name "Net-(IC27B-MICVDD)") (class "Default")
      (node (ref "C182") (pin "2") (pinfunction "2_2") (pintype "passive"))
      (node (ref "C183") (pin "2") (pinfunction "2_2") (pintype "passive"))
      (node (ref "IC27") (pin "19") (pinfunction "MICVDD_19") (pintype "passive"))
      (node (ref "L31") (pin "2") (pinfunction "2_2") (pintype "passive"))
    )
    (net (code "72") (name "Net-(IC27B-VMIDC)") (class "Default")
      (node (ref "C184") (pin "2") (pinfunction "2_2") (pintype "passive"))
      (node (ref "IC27") (pin "21") (pinfunction "VMIDC_21") (pintype "passive"))
    )
    (net (code "73") (name "unconnected-(IC27A-GPIO1_{slash}_IRQ-Pad1)") (class "Default")
      (node (ref "IC27") (pin "1") (pinfunction "GPIO1_/_IRQ_1") (pintype "passive+no_connect"))
    )
    (net (code "74") (name "unconnected-(IC27A-IN1R_{slash}_DMICDAT2-Pad25)") (class "Default")
      (node (ref "IC27") (pin "25") (pinfunction "IN1R_/_DMICDAT2_25") (pintype "passive+no_connect"))
    )
  )
)
